# neato.net
KiCad netlist of a schematic drawn in EAGLE
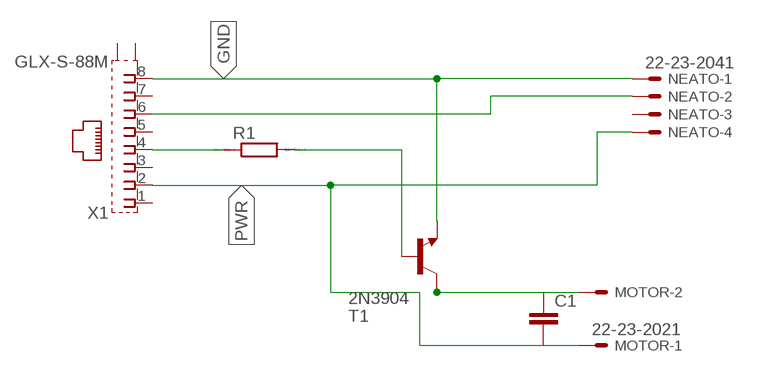
[diagram p0: schematic, sheet 1]

(export (version "E")
  (design (tool "Eeschema 10.0.6"))
  (components
    (comp (ref "C1")
      (value "C2,5-3")
      (footprint "eagle-import:C2.5-3")
      (libsource (lib "eagle-import") (part "C2,5-3"))
    )
    (comp (ref "MOTOR")
      (value "22-23-2021")
      (footprint "eagle-import:22-23-2021")
      (fields (field (name "MF") "MOLEX"))
      (libsource (lib "eagle-import") (part "22-23-2021"))
    )
    (comp (ref "NEATO")
      (value "22-23-2041")
      (footprint "eagle-import:22-23-2041")
      (fields (field (name "MF") "MOLEX"))
      (libsource (lib "eagle-import") (part "22-23-2041"))
    )
    (comp (ref "R1")
      (value "R0207/10")
      (footprint "eagle-import:0207_10")
      (libsource (lib "eagle-import") (part "R0207/10"))
    )
    (comp (ref "T1")
      (value "2N3904")
      (footprint "eagle-import:TO92")
      (libsource (lib "eagle-import") (part "2N3904"))
    )
    (comp (ref "X1")
      (value "GLX-S-88M")
      (footprint "eagle-import:GLX-S-88M")
      (libsource (lib "eagle-import") (part "GLX-S-88M"))
    )
  )
  (nets
    (net (code "1") (name "GND") (class "Default")
      (node (ref "NEATO") (pin "1") (pinfunction "S_1") (pintype "passive"))
      (node (ref "T1") (pin "3") (pinfunction "E_3") (pintype "passive"))
      (node (ref "X1") (pin "8") (pinfunction "8_8") (pintype "passive"))
    )
    (net (code "2") (name "Net-(MOTORB-S)") (class "Default")
      (node (ref "C1") (pin "1") (pinfunction "1_1") (pintype "passive"))
      (node (ref "MOTOR") (pin "2") (pinfunction "S_2") (pintype "passive"))
      (node (ref "T1") (pin "1") (pinfunction "C_1") (pintype "passive"))
    )
    (net (code "3") (name "Net-(NEATOB-S)") (class "Default")
      (node (ref "NEATO") (pin "2") (pinfunction "S_2") (pintype "passive"))
      (node (ref "X1") (pin "6") (pinfunction "6_6") (pintype "passive"))
    )
    (net (code "4") (name "Net-(R1-Pad1)") (class "Default")
      (node (ref "R1") (pin "1") (pinfunction "1_1") (pintype "passive"))
      (node (ref "X1") (pin "4") (pinfunction "4_4") (pintype "passive"))
    )
    (net (code "5") (name "Net-(T1-B)") (class "Default")
      (node (ref "R1") (pin "2") (pinfunction "2_2") (pintype "passive"))
      (node (ref "T1") (pin "2") (pinfunction "B_2") (pintype "passive"))
    )
    (net (code "6") (name "PWR") (class "Default")
      (node (ref "C1") (pin "2") (pinfunction "2_2") (pintype "passive"))
      (node (ref "MOTOR") (pin "1") (pinfunction "S_1") (pintype "passive"))
      (node (ref "NEATO") (pin "4") (pinfunction "S_4") (pintype "passive"))
      (node (ref "X1") (pin "2") (pinfunction "2_2") (pintype "passive"))
    )
    (net (code "7") (name "unconnected-(NEATOC-S-Pad3)") (class "Default")
      (node (ref "NEATO") (pin "3") (pinfunction "S_3") (pintype "passive"))
    )
    (net (code "8") (name "unconnected-(X1-Pad1)") (class "Default")
      (node (ref "X1") (pin "1") (pinfunction "1_1") (pintype "passive"))
    )
    (net (code "9") (name "unconnected-(X1-Pad3)") (class "Default")
      (node (ref "X1") (pin "3") (pinfunction "3_3") (pintype "passive"))
    )
    (net (code "10") (name "unconnected-(X1-Pad5)") (class "Default")
      (node (ref "X1") (pin "5") (pinfunction "5_5") (pintype "passive"))
    )
    (net (code "11") (name "unconnected-(X1-Pad7)") (class "Default")
      (node (ref "X1") (pin "7") (pinfunction "7_7") (pintype "passive"))
    )
    (net (code "12") (name "unconnected-(X1-PadS1)") (class "Default")
      (node (ref "X1") (pin "S1") (pinfunction "S1_S1") (pintype "passive"))
    )
    (net (code "13") (name "unconnected-(X1-PadS2)") (class "Default")
      (node (ref "X1") (pin "S2") (pinfunction "S2_S2") (pintype "passive"))
    )
  )
)
